# Connector.net
KiCad netlist of a schematic drawn in Altium Designer
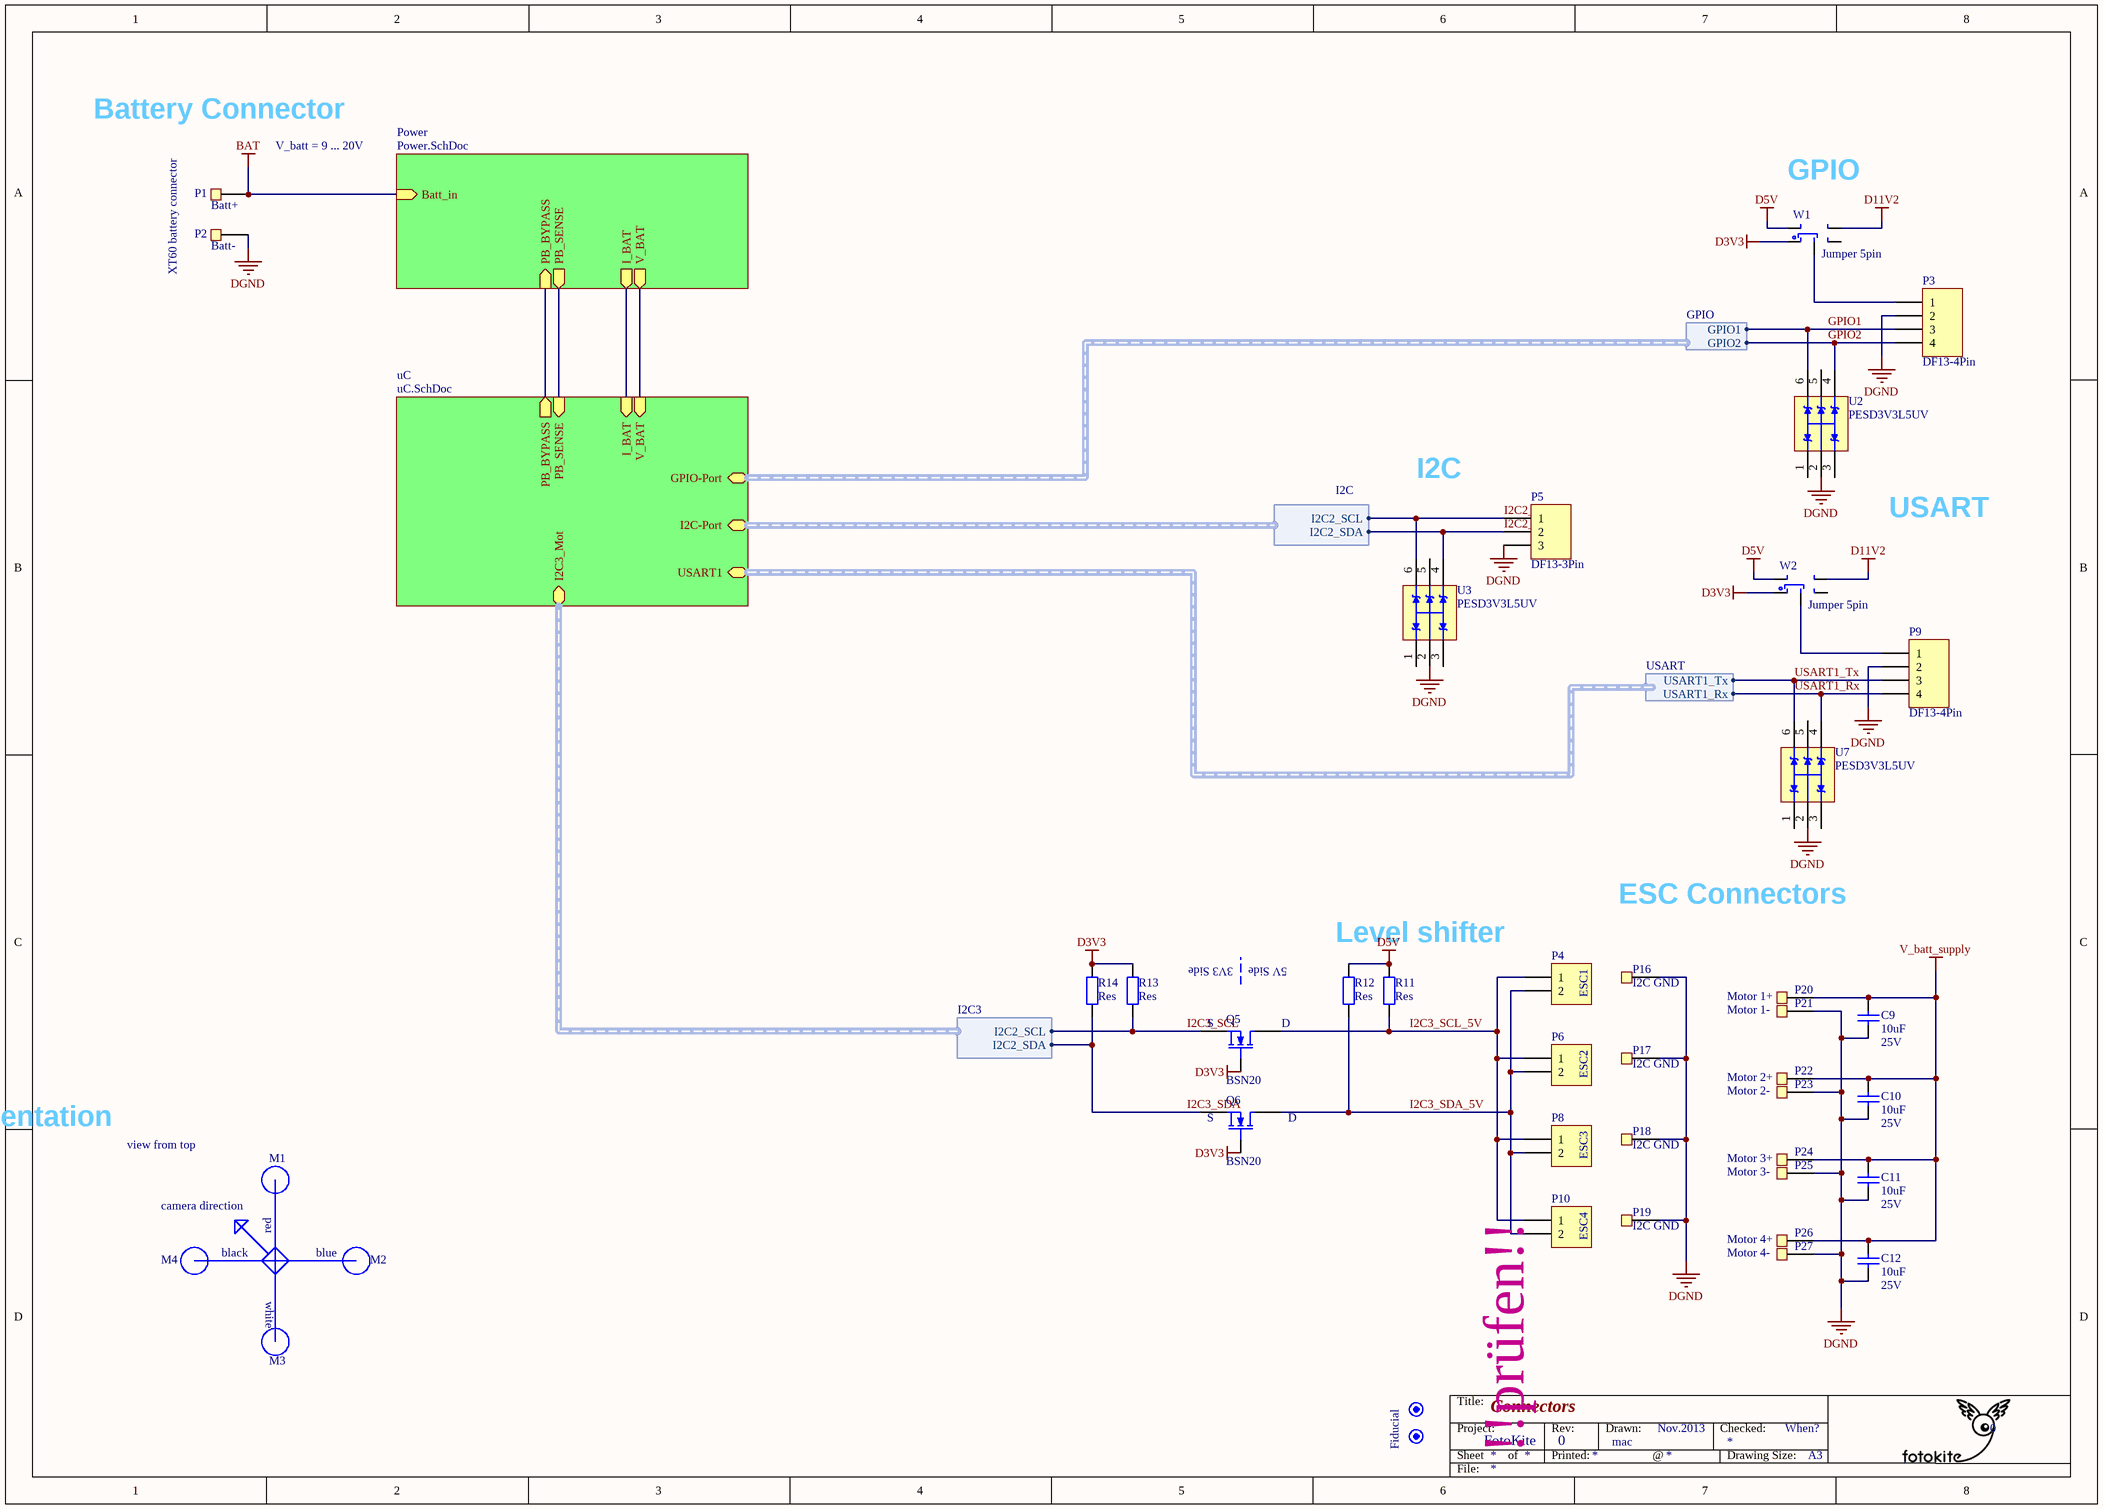
[diagram p0: Connector.SchDoc]

(export (version "E")
  (design (tool "Eeschema 10.0.6"))
  (components
    (comp (ref "C9")
      (value "10uF")
      (footprint "CAP_0805i_2012m -N")
      (description "capacitor")
      (fields (field (name "NOTE") "25V"))
      (libsource (lib "IDSC std generic parts ") (part "Cap"))
    )
    (comp (ref "C10")
      (value "10uF")
      (footprint "CAP_0805i_2012m -N")
      (description "capacitor")
      (fields (field (name "NOTE") "25V"))
      (libsource (lib "IDSC std generic parts ") (part "Cap"))
    )
    (comp (ref "C11")
      (value "10uF")
      (footprint "CAP_0805i_2012m -N")
      (description "capacitor")
      (fields (field (name "NOTE") "25V"))
      (libsource (lib "IDSC std generic parts ") (part "Cap"))
    )
    (comp (ref "C12")
      (value "10uF")
      (footprint "CAP_0805i_2012m -N")
      (description "capacitor")
      (fields (field (name "NOTE") "25V"))
      (libsource (lib "IDSC std generic parts ") (part "Cap"))
    )
    (comp (ref "FID1")
      (value "Fiducial")
      (footprint "Fiducial 2 sides")
      (description "Fiducial mark for automatic pcb population")
      (libsource (lib "IDSC MechanicalParts") (part "Fiducial"))
    )
    (comp (ref "FID2")
      (value "Fiducial")
      (footprint "Fiducial 2 sides")
      (description "Fiducial mark for automatic pcb population")
      (libsource (lib "IDSC MechanicalParts") (part "Fiducial"))
    )
    (comp (ref "P1")
      (value "Batt+")
      (footprint "Pad_3x6mm")
      (description "Single Pad or Testpoint")
      (libsource (lib "") (part "Pad_1"))
    )
    (comp (ref "P2")
      (value "Batt-")
      (footprint "Pad_3x6mm")
      (description "Single Pad or Testpoint")
      (libsource (lib "") (part "Pad_1"))
    )
    (comp (ref "P3")
      (value "DF13-4Pin")
      (footprint "Hirose_DF13_SMT_RA_N4")
      (description "Hirose_DF13_SMT_RA_N4")
      (libsource (lib "IDSC std connectors") (part "DF13-4Pin"))
    )
    (comp (ref "P4")
      (value "ESC1")
      (footprint "Hirose_DF13_SMT_RA_N2")
      (description "Hirose_DF13_SMT_RA_N2")
      (libsource (lib "IDSC std connectors") (part "DF13-2Pin"))
    )
    (comp (ref "P5")
      (value "DF13-3Pin")
      (footprint "Hirose_DF13_SMT_RA_N3")
      (description "Hirose_DF13_SMT_RA_N4")
      (libsource (lib "IDSC std connectors") (part "DF13-3Pin"))
    )
    (comp (ref "P6")
      (value "ESC2")
      (footprint "Hirose_DF13_SMT_RA_N2")
      (description "Hirose_DF13_SMT_RA_N2")
      (libsource (lib "IDSC std connectors") (part "DF13-2Pin"))
    )
    (comp (ref "P8")
      (value "ESC3")
      (footprint "Hirose_DF13_SMT_RA_N2")
      (description "Hirose_DF13_SMT_RA_N2")
      (libsource (lib "IDSC std connectors") (part "DF13-2Pin"))
    )
    (comp (ref "P9")
      (value "DF13-4Pin")
      (footprint "Hirose_DF13_SMT_RA_N4")
      (description "Hirose_DF13_SMT_RA_N4")
      (libsource (lib "IDSC std connectors") (part "DF13-4Pin"))
    )
    (comp (ref "P10")
      (value "ESC4")
      (footprint "Hirose_DF13_SMT_RA_N2")
      (description "Hirose_DF13_SMT_RA_N2")
      (libsource (lib "IDSC std connectors") (part "DF13-2Pin"))
    )
    (comp (ref "P16")
      (value "I2C GND")
      (footprint "Pad_0603")
      (description "Single Pad or Testpoint")
      (libsource (lib "IDSC std connectors") (part "Pad"))
    )
    (comp (ref "P17")
      (value "I2C GND")
      (footprint "Pad_0603")
      (description "Single Pad or Testpoint")
      (libsource (lib "IDSC std connectors") (part "Pad"))
    )
    (comp (ref "P18")
      (value "I2C GND")
      (footprint "Pad_0603")
      (description "Single Pad or Testpoint")
      (libsource (lib "IDSC std connectors") (part "Pad"))
    )
    (comp (ref "P19")
      (value "I2C GND")
      (footprint "Pad_0603")
      (description "Single Pad or Testpoint")
      (libsource (lib "IDSC std connectors") (part "Pad"))
    )
    (comp (ref "P20")
      (value "Motor 1+")
      (footprint "Pad_3x4.5mm")
      (description "Single Pad or Testpoint")
      (libsource (lib "IDSC std connectors") (part "Pad"))
    )
    (comp (ref "P21")
      (value "Motor 1-")
      (footprint "Pad_3x4.5mm")
      (description "Single Pad or Testpoint")
      (libsource (lib "IDSC std connectors") (part "Pad"))
    )
    (comp (ref "P22")
      (value "Motor 2+")
      (footprint "Pad_3x4.5mm")
      (description "Single Pad or Testpoint")
      (libsource (lib "IDSC std connectors") (part "Pad"))
    )
    (comp (ref "P23")
      (value "Motor 2-")
      (footprint "Pad_3x4.5mm")
      (description "Single Pad or Testpoint")
      (libsource (lib "IDSC std connectors") (part "Pad"))
    )
    (comp (ref "P24")
      (value "Motor 3+")
      (footprint "Pad_3x4.5mm")
      (description "Single Pad or Testpoint")
      (libsource (lib "IDSC std connectors") (part "Pad"))
    )
    (comp (ref "P25")
      (value "Motor 3-")
      (footprint "Pad_3x4.5mm")
      (description "Single Pad or Testpoint")
      (libsource (lib "IDSC std connectors") (part "Pad"))
    )
    (comp (ref "P26")
      (value "Motor 4+")
      (footprint "Pad_3x4.5mm")
      (description "Single Pad or Testpoint")
      (libsource (lib "IDSC std connectors") (part "Pad"))
    )
    (comp (ref "P27")
      (value "Motor 4-")
      (footprint "Pad_3x4.5mm")
      (description "Single Pad or Testpoint")
      (libsource (lib "IDSC std connectors") (part "Pad"))
    )
    (comp (ref "Q5")
      (value "BSN20")
      (footprint "SOT23-N")
      (description "N-Channel MOSFET")
      (fields (field (name "DIGI-KEY PART NO.") "BSN20-7DICT-ND"))
      (libsource (lib "IDSC std generic parts ") (part "MOSFET-N"))
    )
    (comp (ref "Q6")
      (value "BSN20")
      (footprint "SOT23-N")
      (description "N-Channel MOSFET")
      (fields (field (name "DIGI-KEY PART NO.") "BSN20-7DICT-ND"))
      (libsource (lib "IDSC std generic parts ") (part "MOSFET-N"))
    )
    (comp (ref "R11")
      (value "Res")
      (footprint "RES_0402i_1005m -N")
      (description "Resistor")
      (libsource (lib "IDSC std generic parts ") (part "Res"))
    )
    (comp (ref "R12")
      (value "Res")
      (footprint "RES_0402i_1005m -N")
      (description "Resistor")
      (libsource (lib "IDSC std generic parts ") (part "Res"))
    )
    (comp (ref "R13")
      (value "Res")
      (footprint "RES_0402i_1005m -N")
      (description "Resistor")
      (libsource (lib "IDSC std generic parts ") (part "Res"))
    )
    (comp (ref "R14")
      (value "Res")
      (footprint "RES_0402i_1005m -N")
      (description "Resistor")
      (libsource (lib "IDSC std generic parts ") (part "Res"))
    )
    (comp (ref "U2")
      (value "PESD3V3L5UV")
      (footprint "SOT-666-N")
      (description "ESD-protection diode array, 5ch")
      (libsource (lib "IDSC_component_lib") (part "PESDx"))
    )
    (comp (ref "U3")
      (value "PESD3V3L5UV")
      (footprint "SOT-666-N")
      (description "ESD-protection diode array, 5ch")
      (libsource (lib "IDSC_component_lib") (part "PESDx"))
    )
    (comp (ref "U7")
      (value "PESD3V3L5UV")
      (footprint "SOT-666-N")
      (description "ESD-protection diode array, 5ch")
      (libsource (lib "IDSC_component_lib") (part "PESDx"))
    )
    (comp (ref "W1")
      (value "Jumper 5pin")
      (footprint "J5_solder xstyle")
      (description "Jumper 5-pin style")
      (libsource (lib "IDSC std generic parts ") (part "Jumper 5pin"))
    )
    (comp (ref "W2")
      (value "Jumper 5pin")
      (footprint "J5_solder xstyle")
      (description "Jumper 5-pin style")
      (libsource (lib "IDSC std generic parts ") (part "Jumper 5pin"))
    )
  )
  (nets
    (net (code "5") (name "/GPIO1") (class "Default")
      (node (ref "P3") (pin "3") (pinfunction "3_3") (pintype "passive"))
      (node (ref "U2") (pin "6") (pinfunction "c5_6") (pintype "passive"))
    )
    (net (code "6") (name "/GPIO2") (class "Default")
      (node (ref "P3") (pin "4") (pinfunction "4_4") (pintype "passive"))
      (node (ref "U2") (pin "4") (pinfunction "c3_4") (pintype "passive"))
    )
    (net (code "7") (name "/I2C2_SCL") (class "Default")
      (node (ref "P5") (pin "1") (pinfunction "1_1") (pintype "passive"))
      (node (ref "U3") (pin "6") (pinfunction "c5_6") (pintype "passive"))
    )
    (net (code "8") (name "/I2C2_SDA") (class "Default")
      (node (ref "P5") (pin "2") (pinfunction "2_2") (pintype "passive"))
      (node (ref "U3") (pin "4") (pinfunction "c3_4") (pintype "passive"))
    )
    (net (code "9") (name "/I2C3_SCL") (class "Default")
      (node (ref "Q5") (pin "2") (pinfunction "S_2") (pintype "passive"))
      (node (ref "R13") (pin "1") (pinfunction "1_1") (pintype "passive"))
    )
    (net (code "10") (name "/I2C3_SCL_5V") (class "Default")
      (node (ref "P10") (pin "1") (pinfunction "1_1") (pintype "passive"))
      (node (ref "P4") (pin "1") (pinfunction "1_1") (pintype "passive"))
      (node (ref "P6") (pin "1") (pinfunction "1_1") (pintype "passive"))
      (node (ref "P8") (pin "1") (pinfunction "1_1") (pintype "passive"))
      (node (ref "Q5") (pin "3") (pinfunction "D_3") (pintype "passive"))
      (node (ref "R11") (pin "1") (pinfunction "1_1") (pintype "passive"))
    )
    (net (code "11") (name "/I2C3_SDA") (class "Default")
      (node (ref "Q6") (pin "2") (pinfunction "S_2") (pintype "passive"))
      (node (ref "R14") (pin "1") (pinfunction "1_1") (pintype "passive"))
    )
    (net (code "12") (name "/I2C3_SDA_5V") (class "Default")
      (node (ref "P10") (pin "2") (pinfunction "2_2") (pintype "passive"))
      (node (ref "P4") (pin "2") (pinfunction "2_2") (pintype "passive"))
      (node (ref "P6") (pin "2") (pinfunction "2_2") (pintype "passive"))
      (node (ref "P8") (pin "2") (pinfunction "2_2") (pintype "passive"))
      (node (ref "Q6") (pin "3") (pinfunction "D_3") (pintype "passive"))
      (node (ref "R12") (pin "1") (pinfunction "1_1") (pintype "passive"))
    )
    (net (code "16") (name "/USART1_Rx") (class "Default")
      (node (ref "P9") (pin "3") (pinfunction "3_3") (pintype "passive"))
      (node (ref "P9") (pin "4") (pinfunction "4_4") (pintype "passive"))
      (node (ref "U7") (pin "4") (pinfunction "c3_4") (pintype "passive"))
      (node (ref "U7") (pin "6") (pinfunction "c5_6") (pintype "passive"))
    )
    (net (code "22") (name "BAT") (class "Default")
      (node (ref "P1") (pin "1") (pinfunction "1_1") (pintype "passive"))
    )
    (net (code "23") (name "D3V3") (class "Default")
      (node (ref "Q5") (pin "1") (pinfunction "G_1") (pintype "passive"))
      (node (ref "Q6") (pin "1") (pinfunction "G_1") (pintype "passive"))
      (node (ref "R13") (pin "2") (pinfunction "2_2") (pintype "passive"))
      (node (ref "R14") (pin "2") (pinfunction "2_2") (pintype "passive"))
      (node (ref "W1") (pin "1") (pinfunction "C1_1") (pintype "passive"))
      (node (ref "W2") (pin "1") (pinfunction "C1_1") (pintype "passive"))
    )
    (net (code "24") (name "D5V") (class "Default")
      (node (ref "R11") (pin "2") (pinfunction "2_2") (pintype "passive"))
      (node (ref "R12") (pin "2") (pinfunction "2_2") (pintype "passive"))
      (node (ref "W1") (pin "4") (pinfunction "C4_4") (pintype "passive"))
      (node (ref "W2") (pin "4") (pinfunction "C4_4") (pintype "passive"))
    )
    (net (code "25") (name "D11V2") (class "Default")
      (node (ref "W1") (pin "3") (pinfunction "C3_3") (pintype "passive"))
      (node (ref "W2") (pin "3") (pinfunction "C3_3") (pintype "passive"))
    )
    (net (code "26") (name "DGND") (class "Default")
      (node (ref "C10") (pin "1") (pinfunction "1_1") (pintype "passive"))
      (node (ref "C11") (pin "1") (pinfunction "1_1") (pintype "passive"))
      (node (ref "C12") (pin "1") (pinfunction "1_1") (pintype "passive"))
      (node (ref "C9") (pin "1") (pinfunction "1_1") (pintype "passive"))
      (node (ref "P16") (pin "1") (pinfunction "1_1") (pintype "passive"))
      (node (ref "P17") (pin "1") (pinfunction "1_1") (pintype "passive"))
      (node (ref "P18") (pin "1") (pinfunction "1_1") (pintype "passive"))
      (node (ref "P19") (pin "1") (pinfunction "1_1") (pintype "passive"))
      (node (ref "P2") (pin "1") (pinfunction "1_1") (pintype "passive"))
      (node (ref "P21") (pin "1") (pinfunction "1_1") (pintype "passive"))
      (node (ref "P23") (pin "1") (pinfunction "1_1") (pintype "passive"))
      (node (ref "P25") (pin "1") (pinfunction "1_1") (pintype "passive"))
      (node (ref "P27") (pin "1") (pinfunction "1_1") (pintype "passive"))
      (node (ref "P3") (pin "2") (pinfunction "2_2") (pintype "passive"))
      (node (ref "P5") (pin "3") (pinfunction "3_3") (pintype "passive"))
      (node (ref "P9") (pin "2") (pinfunction "2_2") (pintype "passive"))
      (node (ref "U2") (pin "2") (pinfunction "a_2") (pintype "passive"))
      (node (ref "U3") (pin "2") (pinfunction "a_2") (pintype "passive"))
      (node (ref "U7") (pin "2") (pinfunction "a_2") (pintype "passive"))
    )
    (net (code "27") (name "Net-(W1-C5)") (class "Default")
      (node (ref "P3") (pin "1") (pinfunction "1_1") (pintype "passive"))
      (node (ref "W1") (pin "5") (pinfunction "C5_5") (pintype "passive"))
    )
    (net (code "28") (name "Net-(W2-C5)") (class "Default")
      (node (ref "P9") (pin "1") (pinfunction "1_1") (pintype "passive"))
      (node (ref "W2") (pin "5") (pinfunction "C5_5") (pintype "passive"))
    )
    (net (code "29") (name "V_batt_supply") (class "Default")
      (node (ref "C10") (pin "2") (pinfunction "2_2") (pintype "passive"))
      (node (ref "C11") (pin "2") (pinfunction "2_2") (pintype "passive"))
      (node (ref "C12") (pin "2") (pinfunction "2_2") (pintype "passive"))
      (node (ref "C9") (pin "2") (pinfunction "2_2") (pintype "passive"))
      (node (ref "P20") (pin "1") (pinfunction "1_1") (pintype "passive"))
      (node (ref "P22") (pin "1") (pinfunction "1_1") (pintype "passive"))
      (node (ref "P24") (pin "1") (pinfunction "1_1") (pintype "passive"))
      (node (ref "P26") (pin "1") (pinfunction "1_1") (pintype "passive"))
    )
    (net (code "30") (name "unconnected-(U2-c1-Pad1)") (class "Default")
      (node (ref "U2") (pin "1") (pinfunction "c1_1") (pintype "passive"))
    )
    (net (code "31") (name "unconnected-(U2-c2-Pad3)") (class "Default")
      (node (ref "U2") (pin "3") (pinfunction "c2_3") (pintype "passive"))
    )
    (net (code "32") (name "unconnected-(U2-c4-Pad5)") (class "Default")
      (node (ref "U2") (pin "5") (pinfunction "c4_5") (pintype "passive"))
    )
    (net (code "33") (name "unconnected-(U3-c1-Pad1)") (class "Default")
      (node (ref "U3") (pin "1") (pinfunction "c1_1") (pintype "passive"))
    )
    (net (code "34") (name "unconnected-(U3-c2-Pad3)") (class "Default")
      (node (ref "U3") (pin "3") (pinfunction "c2_3") (pintype "passive"))
    )
    (net (code "35") (name "unconnected-(U3-c4-Pad5)") (class "Default")
      (node (ref "U3") (pin "5") (pinfunction "c4_5") (pintype "passive"))
    )
    (net (code "36") (name "unconnected-(U7-c1-Pad1)") (class "Default")
      (node (ref "U7") (pin "1") (pinfunction "c1_1") (pintype "passive"))
    )
    (net (code "37") (name "unconnected-(U7-c2-Pad3)") (class "Default")
      (node (ref "U7") (pin "3") (pinfunction "c2_3") (pintype "passive"))
    )
    (net (code "38") (name "unconnected-(U7-c4-Pad5)") (class "Default")
      (node (ref "U7") (pin "5") (pinfunction "c4_5") (pintype "passive"))
    )
    (net (code "39") (name "unconnected-(W1-C2-Pad2)") (class "Default")
      (node (ref "W1") (pin "2") (pinfunction "C2_2") (pintype "passive"))
    )
    (net (code "40") (name "unconnected-(W2-C2-Pad2)") (class "Default")
      (node (ref "W2") (pin "2") (pinfunction "C2_2") (pintype "passive"))
    )
  )
)
